# 03-4G.net
KiCad netlist of a schematic drawn in Altium Designer
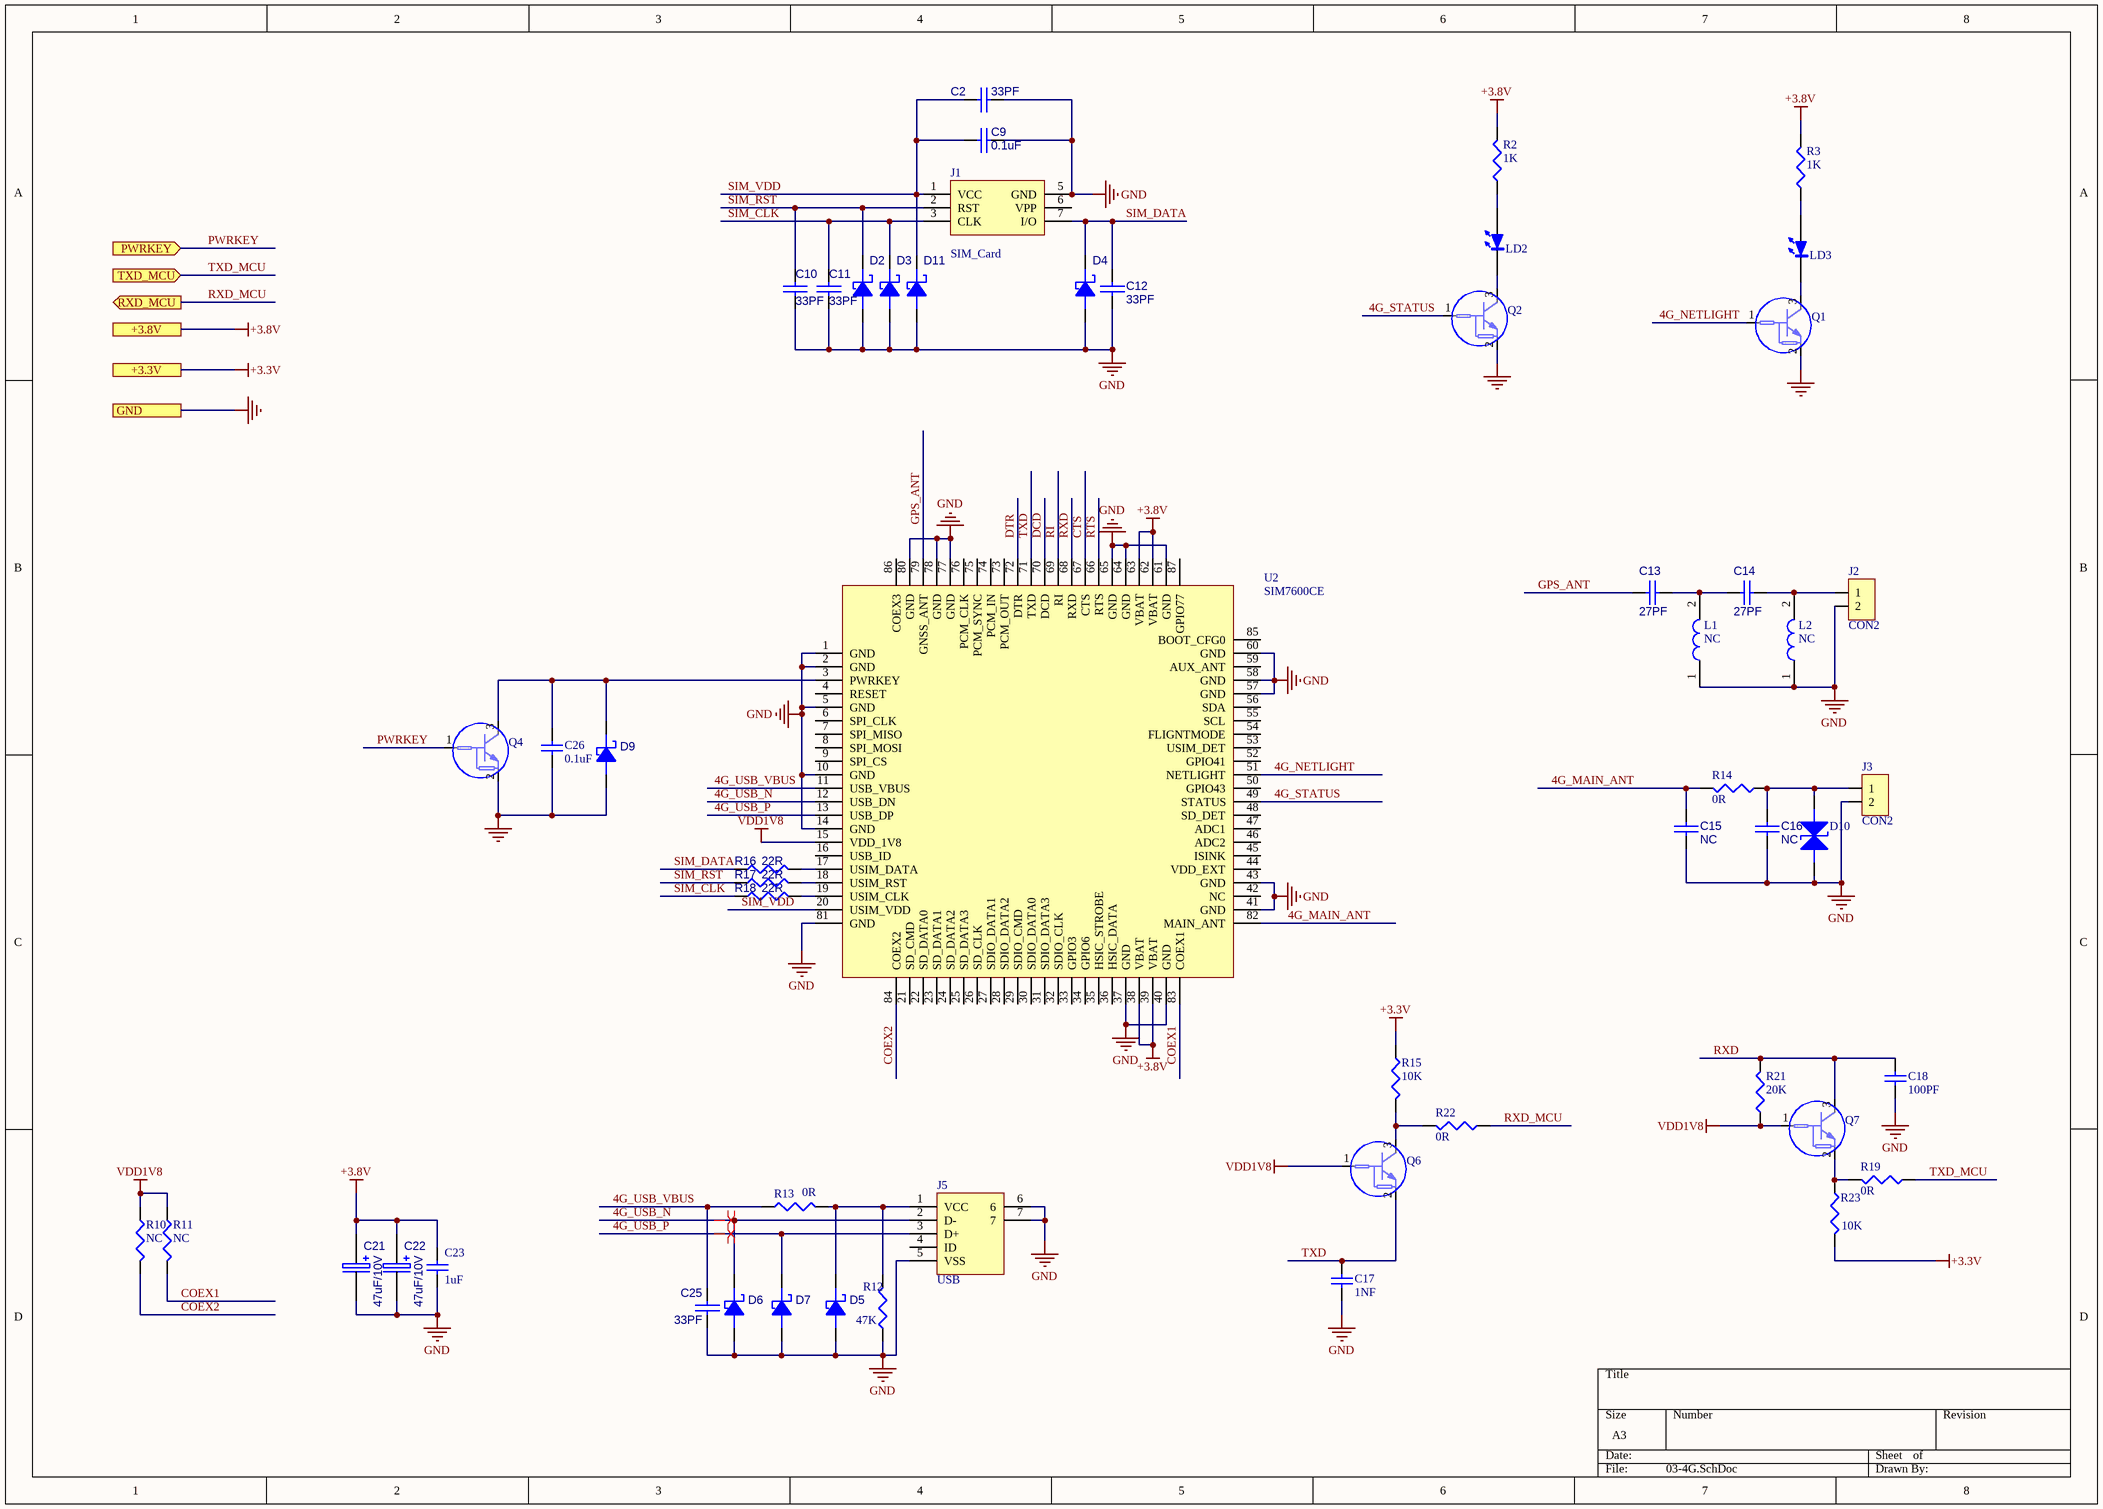
[diagram p0: 03-4G.SchDoc]

(export (version "E")
  (design (tool "Eeschema 10.0.6"))
  (components
    (comp (ref "C2")
      (value "33PF")
      (footprint "0603_C")
      (description "CAP")
      (libsource (lib "") (part "CAP_1"))
    )
    (comp (ref "C9")
      (value "0.1uF")
      (footprint "0603_C")
      (description "CAP")
      (libsource (lib "") (part "CAP_1"))
    )
    (comp (ref "C10")
      (value "33PF")
      (footprint "0603_C")
      (description "CAP")
      (libsource (lib "*") (part "CAP"))
    )
    (comp (ref "C11")
      (value "33PF")
      (footprint "0603_C")
      (description "CAP")
      (libsource (lib "*") (part "CAP"))
    )
    (comp (ref "C12")
      (value "33PF")
      (footprint "0603_C")
      (description "CAP")
      (libsource (lib "*") (part "CAP"))
    )
    (comp (ref "C13")
      (value "27PF")
      (footprint "0402")
      (description "CAP")
      (libsource (lib "") (part "CAP_1"))
    )
    (comp (ref "C14")
      (value "27PF")
      (footprint "0402")
      (description "CAP")
      (libsource (lib "") (part "CAP_1"))
    )
    (comp (ref "C15") (value "NC") (footprint "0402") (description "CAP") (libsource (lib "*") (part "CAP")))
    (comp (ref "C16") (value "NC") (footprint "0402") (description "CAP") (libsource (lib "*") (part "CAP")))
    (comp (ref "C17")
      (value "1NF")
      (footprint "0603_C")
      (description "Capacitor")
      (fields (field (name "PUBLISHER") "Altium Limited"))
      (libsource (lib "EP_MCB_V3.00") (part "Cap Semi"))
    )
    (comp (ref "C18")
      (value "100PF")
      (footprint "0603_C")
      (description "Capacitor")
      (fields (field (name "PUBLISHER") "Altium Limited"))
      (libsource (lib "EP_MCB_V3.00") (part "Cap Semi"))
    )
    (comp (ref "C21")
      (value "47uF/10V")
      (footprint "C_TAN_B")
      (description "E-CAP")
      (libsource (lib "*") (part "ECAP"))
    )
    (comp (ref "C22")
      (value "47uF/10V")
      (footprint "C_TAN_B")
      (description "E-CAP")
      (libsource (lib "*") (part "ECAP"))
    )
    (comp (ref "C23")
      (value "1uF")
      (footprint "0603_C")
      (description "Capacitor")
      (fields (field (name "PUBLISHER") "Altium Limited"))
      (libsource (lib "EP_MCB_V3.00") (part "Cap Semi"))
    )
    (comp (ref "C25")
      (value "33PF")
      (footprint "0603_C")
      (description "CAP")
      (libsource (lib "*") (part "CAP"))
    )
    (comp (ref "C26")
      (value "0.1uF")
      (footprint "0603_C")
      (description "Capacitor")
      (fields (field (name "PUBLISHER") "Altium Limited"))
      (libsource (lib "EP_MCB_V3.00") (part "Cap Semi"))
    )
    (comp (ref "D2")
      (value "ESD9M5.0ST5G")
      (footprint "SOD-923")
      (libsource (lib "EP_MCB_V4.1") (part "DIODE SCHOTTKY"))
    )
    (comp (ref "D3")
      (value "ESD9M5.0ST5G")
      (footprint "SOD-923")
      (libsource (lib "EP_MCB_V4.1") (part "DIODE SCHOTTKY"))
    )
    (comp (ref "D4")
      (value "ESD9M5.0ST5G")
      (footprint "SOD-923")
      (libsource (lib "EP_MCB_V4.1") (part "DIODE SCHOTTKY"))
    )
    (comp (ref "D5")
      (value "PESD12VS1UB")
      (footprint "SOD523")
      (libsource (lib "EP_MCB_V4.1") (part "DIODE SCHOTTKY"))
    )
    (comp (ref "D6")
      (value "ESD9L5.0ST5G")
      (footprint "SOD-923")
      (libsource (lib "EP_MCB_V4.1") (part "DIODE SCHOTTKY"))
    )
    (comp (ref "D7")
      (value "ESD9L5.0ST5G")
      (footprint "SOD-923")
      (libsource (lib "EP_MCB_V4.1") (part "DIODE SCHOTTKY"))
    )
    (comp (ref "D9")
      (value "ESD9M5.0ST5G")
      (footprint "SOD-923")
      (libsource (lib "EP_MCB_V4.1") (part "DIODE SCHOTTKY"))
    )
    (comp (ref "D10")
      (value "LXES15AAA1-153")
      (footprint "0402")
      (libsource (lib "MySchlib") (part "DIODE TVS BI-DIR"))
    )
    (comp (ref "D11")
      (value "ESD9M5.0ST5G")
      (footprint "SOD-923")
      (libsource (lib "EP_MCB_V4.1") (part "DIODE SCHOTTKY"))
    )
    (comp (ref "J1")
      (value "SIM_Card")
      (footprint "MicroSIM-6")
      (libsource (lib "MySchlib") (part "SIM_Card"))
    )
    (comp (ref "J2") (value "CON2") (footprint "RF-Z") (libsource (lib "MySchlib") (part "CON2")))
    (comp (ref "J3") (value "CON2") (footprint "RF-Z") (libsource (lib "MySchlib") (part "CON2")))
    (comp (ref "J5") (value "USB") (libsource (lib "MySchlib") (part "USB-M")))
    (comp (ref "L1") (value "NC") (footprint "0402") (libsource (lib "MySchlib") (part "L")))
    (comp (ref "L2") (value "NC") (footprint "0402") (libsource (lib "MySchlib") (part "L")))
    (comp (ref "LD2")
      (value "WHITE")
      (footprint "LED_0603")
      (description "LED")
      (libsource (lib "*") (part "LED"))
    )
    (comp (ref "LD3")
      (value "WHITE")
      (footprint "LED_0603")
      (description "LED")
      (libsource (lib "*") (part "LED"))
    )
    (comp (ref "Q1")
      (value "DTC143ZEBTL")
      (footprint "SC-85")
      (libsource (lib "MySchlib") (part "DTC143ZETL"))
    )
    (comp (ref "Q2")
      (value "DTC143ZEBTL")
      (footprint "SC-85")
      (libsource (lib "MySchlib") (part "DTC143ZETL"))
    )
    (comp (ref "Q4")
      (value "DTC143ZEBTL")
      (footprint "SC-85")
      (libsource (lib "MySchlib") (part "DTC143ZETL"))
    )
    (comp (ref "Q6")
      (value "DTC143ZEBTL")
      (footprint "SC-85")
      (libsource (lib "MySchlib") (part "DTC143ZETL"))
    )
    (comp (ref "Q7")
      (value "DTC143ZEBTL")
      (footprint "SC-85")
      (libsource (lib "MySchlib") (part "DTC143ZETL"))
    )
    (comp (ref "R2") (value "1K") (footprint "0603_R") (libsource (lib "MySchlib") (part "RES1")))
    (comp (ref "R3") (value "1K") (footprint "0603_R") (libsource (lib "MySchlib") (part "RES1")))
    (comp (ref "R10") (value "NC") (footprint "0603_R") (libsource (lib "MySchlib") (part "RES1")))
    (comp (ref "R11") (value "NC") (footprint "0603_R") (libsource (lib "MySchlib") (part "RES1")))
    (comp (ref "R12") (value "47K") (footprint "0603_R") (libsource (lib "MySchlib") (part "RES1")))
    (comp (ref "R13") (value "0R") (footprint "0402") (libsource (lib "MySchlib") (part "RES1")))
    (comp (ref "R14") (value "0R") (footprint "0402") (libsource (lib "MySchlib") (part "RES1")))
    (comp (ref "R15") (value "10K") (footprint "0603_R") (libsource (lib "MySchlib") (part "RES1")))
    (comp (ref "R16")
      (value "22R")
      (footprint "0603_R")
      (description "RESISTOR")
      (libsource (lib "*") (part "R0.25W"))
    )
    (comp (ref "R17")
      (value "22R")
      (footprint "0603_R")
      (description "RESISTOR")
      (libsource (lib "*") (part "R0.25W"))
    )
    (comp (ref "R18")
      (value "22R")
      (footprint "0603_R")
      (description "RESISTOR")
      (libsource (lib "*") (part "R0.25W"))
    )
    (comp (ref "R19") (value "0R") (footprint "0603_R") (libsource (lib "MySchlib") (part "RES1")))
    (comp (ref "R21") (value "20K") (footprint "0603_R") (libsource (lib "MySchlib") (part "RES1")))
    (comp (ref "R22") (value "0R") (footprint "0603_R") (libsource (lib "MySchlib") (part "RES1")))
    (comp (ref "R23") (value "10K") (footprint "0603_R") (libsource (lib "MySchlib") (part "RES1")))
    (comp (ref "U2") (value "SIM7600CE") (footprint "SIM7600") (libsource (lib "MySchlib") (part "SIM7600")))
  )
  (nets
    (net (code "1") (name "+3.3V") (class "Default")
      (node (ref "R15") (pin "1") (pinfunction "1_1") (pintype "passive"))
      (node (ref "R23") (pin "2") (pinfunction "2_2") (pintype "passive"))
    )
    (net (code "2") (name "+3.8V") (class "Default")
      (node (ref "C21") (pin "1") (pinfunction "+_1") (pintype "passive"))
      (node (ref "C22") (pin "1") (pinfunction "+_1") (pintype "passive"))
      (node (ref "C23") (pin "2") (pinfunction "2_2") (pintype "passive"))
      (node (ref "R2") (pin "1") (pinfunction "1_1") (pintype "passive"))
      (node (ref "R3") (pin "1") (pinfunction "1_1") (pintype "passive"))
      (node (ref "U2") (pin "38") (pinfunction "VBAT_38") (pintype "passive"))
      (node (ref "U2") (pin "39") (pinfunction "VBAT_39") (pintype "passive"))
      (node (ref "U2") (pin "62") (pinfunction "VBAT_62") (pintype "passive"))
      (node (ref "U2") (pin "63") (pinfunction "VBAT_63") (pintype "passive"))
    )
    (net (code "3") (name "/4G_MAIN_ANT") (class "Default")
      (node (ref "C15") (pin "2") (pinfunction "2_2") (pintype "passive"))
      (node (ref "R14") (pin "2") (pinfunction "2_2") (pintype "passive"))
      (node (ref "U2") (pin "82") (pinfunction "MAIN_ANT_82") (pintype "passive"))
    )
    (net (code "4") (name "/4G_NETLIGHT") (class "Default")
      (node (ref "Q1") (pin "1") (pinfunction "B_1") (pintype "passive"))
      (node (ref "U2") (pin "51") (pinfunction "NETLIGHT_51") (pintype "passive"))
    )
    (net (code "5") (name "/4G_STATUS") (class "Default")
      (node (ref "Q2") (pin "1") (pinfunction "B_1") (pintype "passive"))
      (node (ref "U2") (pin "49") (pinfunction "STATUS_49") (pintype "passive"))
    )
    (net (code "6") (name "/4G_USB_N") (class "Default")
      (node (ref "D6") (pin "2") (pinfunction "CATHODE_2") (pintype "passive"))
      (node (ref "J5") (pin "2") (pinfunction "D-_2") (pintype "passive"))
      (node (ref "U2") (pin "12") (pinfunction "USB_DN_12") (pintype "passive"))
    )
    (net (code "7") (name "/4G_USB_P") (class "Default")
      (node (ref "D7") (pin "2") (pinfunction "CATHODE_2") (pintype "passive"))
      (node (ref "J5") (pin "3") (pinfunction "D+_3") (pintype "passive"))
      (node (ref "U2") (pin "13") (pinfunction "USB_DP_13") (pintype "passive"))
    )
    (net (code "8") (name "/4G_USB_VBUS") (class "Default")
      (node (ref "C25") (pin "1") (pinfunction "1_1") (pintype "passive"))
      (node (ref "R13") (pin "1") (pinfunction "1_1") (pintype "passive"))
      (node (ref "U2") (pin "11") (pinfunction "USB_VBUS_11") (pintype "passive"))
    )
    (net (code "9") (name "/COEX1") (class "Default")
      (node (ref "R11") (pin "2") (pinfunction "2_2") (pintype "passive"))
      (node (ref "U2") (pin "83") (pinfunction "COEX1_83") (pintype "passive"))
    )
    (net (code "10") (name "/COEX2") (class "Default")
      (node (ref "R10") (pin "2") (pinfunction "2_2") (pintype "passive"))
      (node (ref "U2") (pin "84") (pinfunction "COEX2_84") (pintype "passive"))
    )
    (net (code "11") (name "/CTS") (class "Default")
      (node (ref "U2") (pin "67") (pinfunction "CTS_67") (pintype "passive"))
    )
    (net (code "12") (name "/DCD") (class "Default")
      (node (ref "U2") (pin "70") (pinfunction "DCD_70") (pintype "passive"))
    )
    (net (code "13") (name "/DTR") (class "Default")
      (node (ref "U2") (pin "72") (pinfunction "DTR_72") (pintype "passive"))
    )
    (net (code "14") (name "/GPS_ANT") (class "Default")
      (node (ref "C13") (pin "1") (pinfunction "1_1") (pintype "passive"))
      (node (ref "U2") (pin "79") (pinfunction "GNSS_ANT_79") (pintype "passive"))
    )
    (net (code "15") (name "/PWRKEY") (class "Default")
      (node (ref "Q4") (pin "1") (pinfunction "B_1") (pintype "passive"))
    )
    (net (code "16") (name "/RI") (class "Default")
      (node (ref "U2") (pin "69") (pinfunction "RI_69") (pintype "passive"))
    )
    (net (code "17") (name "/RTS") (class "Default")
      (node (ref "U2") (pin "66") (pinfunction "RTS_66") (pintype "passive"))
    )
    (net (code "18") (name "/RXD") (class "Default")
      (node (ref "C18") (pin "2") (pinfunction "2_2") (pintype "passive"))
      (node (ref "Q7") (pin "3") (pinfunction "C_3") (pintype "passive"))
      (node (ref "R21") (pin "2") (pinfunction "2_2") (pintype "passive"))
      (node (ref "U2") (pin "68") (pinfunction "RXD_68") (pintype "passive"))
    )
    (net (code "19") (name "/RXD_MCU") (class "Default")
      (node (ref "R22") (pin "1") (pinfunction "1_1") (pintype "passive"))
    )
    (net (code "20") (name "/SIM_CLK") (class "Default")
      (node (ref "C11") (pin "2") (pinfunction "2_2") (pintype "passive"))
      (node (ref "D3") (pin "2") (pinfunction "CATHODE_2") (pintype "passive"))
      (node (ref "J1") (pin "3") (pinfunction "CLK_3") (pintype "passive"))
      (node (ref "R18") (pin "1") (pinfunction "1_1") (pintype "passive"))
    )
    (net (code "21") (name "/SIM_DATA") (class "Default")
      (node (ref "C12") (pin "2") (pinfunction "2_2") (pintype "passive"))
      (node (ref "D4") (pin "2") (pinfunction "CATHODE_2") (pintype "passive"))
      (node (ref "J1") (pin "7") (pinfunction "I/O_7") (pintype "passive"))
      (node (ref "R16") (pin "1") (pinfunction "1_1") (pintype "passive"))
    )
    (net (code "22") (name "/SIM_RST") (class "Default")
      (node (ref "C10") (pin "2") (pinfunction "2_2") (pintype "passive"))
      (node (ref "D2") (pin "2") (pinfunction "CATHODE_2") (pintype "passive"))
      (node (ref "J1") (pin "2") (pinfunction "RST_2") (pintype "passive"))
      (node (ref "R17") (pin "1") (pinfunction "1_1") (pintype "passive"))
    )
    (net (code "23") (name "/SIM_VDD") (class "Default")
      (node (ref "C2") (pin "1") (pinfunction "1_1") (pintype "passive"))
      (node (ref "C9") (pin "1") (pinfunction "1_1") (pintype "passive"))
      (node (ref "D11") (pin "2") (pinfunction "CATHODE_2") (pintype "passive"))
      (node (ref "J1") (pin "1") (pinfunction "VCC_1") (pintype "passive"))
      (node (ref "U2") (pin "20") (pinfunction "USIM_VDD_20") (pintype "passive"))
    )
    (net (code "24") (name "/TXD") (class "Default")
      (node (ref "C17") (pin "1") (pinfunction "1_1") (pintype "passive"))
      (node (ref "Q6") (pin "2") (pinfunction "E_2") (pintype "passive"))
      (node (ref "U2") (pin "71") (pinfunction "TXD_71") (pintype "passive"))
    )
    (net (code "25") (name "/TXD_MCU") (class "Default")
      (node (ref "R19") (pin "1") (pinfunction "1_1") (pintype "passive"))
    )
    (net (code "26") (name "GND") (class "Default")
      (node (ref "C10") (pin "1") (pinfunction "1_1") (pintype "passive"))
      (node (ref "C11") (pin "1") (pinfunction "1_1") (pintype "passive"))
      (node (ref "C12") (pin "1") (pinfunction "1_1") (pintype "passive"))
      (node (ref "C15") (pin "1") (pinfunction "1_1") (pintype "passive"))
      (node (ref "C16") (pin "1") (pinfunction "1_1") (pintype "passive"))
      (node (ref "C17") (pin "2") (pinfunction "2_2") (pintype "passive"))
      (node (ref "C18") (pin "1") (pinfunction "1_1") (pintype "passive"))
      (node (ref "C2") (pin "2") (pinfunction "2_2") (pintype "passive"))
      (node (ref "C21") (pin "2") (pinfunction "-_2") (pintype "passive"))
      (node (ref "C22") (pin "2") (pinfunction "-_2") (pintype "passive"))
      (node (ref "C23") (pin "1") (pinfunction "1_1") (pintype "passive"))
      (node (ref "C25") (pin "2") (pinfunction "2_2") (pintype "passive"))
      (node (ref "C26") (pin "1") (pinfunction "1_1") (pintype "passive"))
      (node (ref "C9") (pin "2") (pinfunction "2_2") (pintype "passive"))
      (node (ref "D10") (pin "2") (pinfunction "2_2") (pintype "passive"))
      (node (ref "D11") (pin "1") (pinfunction "ANODE_1") (pintype "passive"))
      (node (ref "D2") (pin "1") (pinfunction "ANODE_1") (pintype "passive"))
      (node (ref "D3") (pin "1") (pinfunction "ANODE_1") (pintype "passive"))
      (node (ref "D4") (pin "1") (pinfunction "ANODE_1") (pintype "passive"))
      (node (ref "D5") (pin "1") (pinfunction "ANODE_1") (pintype "passive"))
      (node (ref "D6") (pin "1") (pinfunction "ANODE_1") (pintype "passive"))
      (node (ref "D7") (pin "1") (pinfunction "ANODE_1") (pintype "passive"))
      (node (ref "D9") (pin "1") (pinfunction "ANODE_1") (pintype "passive"))
      (node (ref "J1") (pin "5") (pinfunction "GND_5") (pintype "passive"))
      (node (ref "J2") (pin "2") (pinfunction "2_2") (pintype "passive"))
      (node (ref "J3") (pin "2") (pinfunction "2_2") (pintype "passive"))
      (node (ref "J5") (pin "5") (pinfunction "VSS_5") (pintype "passive"))
      (node (ref "J5") (pin "6") (pinfunction "6_6") (pintype "passive"))
      (node (ref "J5") (pin "7") (pinfunction "7_7") (pintype "passive"))
      (node (ref "L1") (pin "1") (pinfunction "1_1") (pintype "passive"))
      (node (ref "L2") (pin "1") (pinfunction "1_1") (pintype "passive"))
      (node (ref "Q1") (pin "2") (pinfunction "E_2") (pintype "passive"))
      (node (ref "Q2") (pin "2") (pinfunction "E_2") (pintype "passive"))
      (node (ref "Q4") (pin "2") (pinfunction "E_2") (pintype "passive"))
      (node (ref "R12") (pin "2") (pinfunction "2_2") (pintype "passive"))
      (node (ref "U2") (pin "1") (pinfunction "GND_1") (pintype "passive"))
      (node (ref "U2") (pin "10") (pinfunction "GND_10") (pintype "passive"))
      (node (ref "U2") (pin "14") (pinfunction "GND_14") (pintype "passive"))
      (node (ref "U2") (pin "2") (pinfunction "GND_2") (pintype "passive"))
      (node (ref "U2") (pin "37") (pinfunction "GND_37") (pintype "passive"))
      (node (ref "U2") (pin "40") (pinfunction "GND_40") (pintype "passive"))
      (node (ref "U2") (pin "41") (pinfunction "GND_41") (pintype "passive"))
      (node (ref "U2") (pin "43") (pinfunction "GND_43") (pintype "passive"))
      (node (ref "U2") (pin "5") (pinfunction "GND_5") (pintype "passive"))
      (node (ref "U2") (pin "57") (pinfunction "GND_57") (pintype "passive"))
      (node (ref "U2") (pin "58") (pinfunction "GND_58") (pintype "passive"))
      (node (ref "U2") (pin "60") (pinfunction "GND_60") (pintype "passive"))
      (node (ref "U2") (pin "61") (pinfunction "GND_61") (pintype "passive"))
      (node (ref "U2") (pin "64") (pinfunction "GND_64") (pintype "passive"))
      (node (ref "U2") (pin "65") (pinfunction "GND_65") (pintype "passive"))
      (node (ref "U2") (pin "77") (pinfunction "GND_77") (pintype "passive"))
      (node (ref "U2") (pin "78") (pinfunction "GND_78") (pintype "passive"))
      (node (ref "U2") (pin "80") (pinfunction "GND_80") (pintype "passive"))
      (node (ref "U2") (pin "81") (pinfunction "GND_81") (pintype "passive"))
    )
    (net (code "27") (name "Net-(C13-Pad2)") (class "Default")
      (node (ref "C13") (pin "2") (pinfunction "2_2") (pintype "passive"))
      (node (ref "C14") (pin "1") (pinfunction "1_1") (pintype "passive"))
      (node (ref "L1") (pin "2") (pinfunction "2_2") (pintype "passive"))
    )
    (net (code "28") (name "Net-(C14-Pad2)") (class "Default")
      (node (ref "C14") (pin "2") (pinfunction "2_2") (pintype "passive"))
      (node (ref "J2") (pin "1") (pinfunction "1_1") (pintype "passive"))
      (node (ref "L2") (pin "2") (pinfunction "2_2") (pintype "passive"))
    )
    (net (code "29") (name "Net-(C16-Pad2)") (class "Default")
      (node (ref "C16") (pin "2") (pinfunction "2_2") (pintype "passive"))
      (node (ref "D10") (pin "1") (pinfunction "1_1") (pintype "passive"))
      (node (ref "J3") (pin "1") (pinfunction "1_1") (pintype "passive"))
      (node (ref "R14") (pin "1") (pinfunction "1_1") (pintype "passive"))
    )
    (net (code "30") (name "Net-(D5-CATHODE)") (class "Default")
      (node (ref "D5") (pin "2") (pinfunction "CATHODE_2") (pintype "passive"))
      (node (ref "J5") (pin "1") (pinfunction "VCC_1") (pintype "passive"))
      (node (ref "R12") (pin "1") (pinfunction "1_1") (pintype "passive"))
      (node (ref "R13") (pin "2") (pinfunction "2_2") (pintype "passive"))
    )
    (net (code "31") (name "Net-(D9-CATHODE)") (class "Default")
      (node (ref "C26") (pin "2") (pinfunction "2_2") (pintype "passive"))
      (node (ref "D9") (pin "2") (pinfunction "CATHODE_2") (pintype "passive"))
      (node (ref "Q4") (pin "3") (pinfunction "C_3") (pintype "passive"))
      (node (ref "U2") (pin "3") (pinfunction "PWRKEY_3") (pintype "passive"))
    )
    (net (code "32") (name "Net-(LD2-PadA)") (class "Default")
      (node (ref "LD2") (pin "A") (pinfunction "A_A") (pintype "passive"))
      (node (ref "R2") (pin "2") (pinfunction "2_2") (pintype "passive"))
    )
    (net (code "33") (name "Net-(LD3-PadA)") (class "Default")
      (node (ref "LD3") (pin "A") (pinfunction "A_A") (pintype "passive"))
      (node (ref "R3") (pin "2") (pinfunction "2_2") (pintype "passive"))
    )
    (net (code "34") (name "Net-(Q1-C)") (class "Default")
      (node (ref "LD3") (pin "K") (pinfunction "K_K") (pintype "passive"))
      (node (ref "Q1") (pin "3") (pinfunction "C_3") (pintype "passive"))
    )
    (net (code "35") (name "Net-(Q2-C)") (class "Default")
      (node (ref "LD2") (pin "K") (pinfunction "K_K") (pintype "passive"))
      (node (ref "Q2") (pin "3") (pinfunction "C_3") (pintype "passive"))
    )
    (net (code "36") (name "Net-(Q6-C)") (class "Default")
      (node (ref "Q6") (pin "3") (pinfunction "C_3") (pintype "passive"))
      (node (ref "R15") (pin "2") (pinfunction "2_2") (pintype "passive"))
      (node (ref "R22") (pin "2") (pinfunction "2_2") (pintype "passive"))
    )
    (net (code "37") (name "Net-(Q7-E)") (class "Default")
      (node (ref "Q7") (pin "2") (pinfunction "E_2") (pintype "passive"))
      (node (ref "R19") (pin "2") (pinfunction "2_2") (pintype "passive"))
      (node (ref "R23") (pin "1") (pinfunction "1_1") (pintype "passive"))
    )
    (net (code "38") (name "Net-(U2-USIM_CLK)") (class "Default")
      (node (ref "R18") (pin "2") (pinfunction "2_2") (pintype "passive"))
      (node (ref "U2") (pin "19") (pinfunction "USIM_CLK_19") (pintype "passive"))
    )
    (net (code "39") (name "Net-(U2-USIM_DATA)") (class "Default")
      (node (ref "R16") (pin "2") (pinfunction "2_2") (pintype "passive"))
      (node (ref "U2") (pin "17") (pinfunction "USIM_DATA_17") (pintype "passive"))
    )
    (net (code "40") (name "Net-(U2-USIM_RST)") (class "Default")
      (node (ref "R17") (pin "2") (pinfunction "2_2") (pintype "passive"))
      (node (ref "U2") (pin "18") (pinfunction "USIM_RST_18") (pintype "passive"))
    )
    (net (code "41") (name "VDD1V8") (class "Default")
      (node (ref "Q6") (pin "1") (pinfunction "B_1") (pintype "passive"))
      (node (ref "Q7") (pin "1") (pinfunction "B_1") (pintype "passive"))
      (node (ref "R10") (pin "1") (pinfunction "1_1") (pintype "passive"))
      (node (ref "R11") (pin "1") (pinfunction "1_1") (pintype "passive"))
      (node (ref "R21") (pin "1") (pinfunction "1_1") (pintype "passive"))
      (node (ref "U2") (pin "15") (pinfunction "VDD_1V8_15") (pintype "passive"))
    )
    (net (code "42") (name "unconnected-(J1-VPP-Pad6)") (class "Default")
      (node (ref "J1") (pin "6") (pinfunction "VPP_6") (pintype "passive"))
    )
    (net (code "43") (name "unconnected-(J5-ID-Pad4)") (class "Default")
      (node (ref "J5") (pin "4") (pinfunction "ID_4") (pintype "passive"))
    )
    (net (code "44") (name "unconnected-(U2-ADC1-Pad47)") (class "Default")
      (node (ref "U2") (pin "47") (pinfunction "ADC1_47") (pintype "passive"))
    )
    (net (code "45") (name "unconnected-(U2-ADC2-Pad46)") (class "Default")
      (node (ref "U2") (pin "46") (pinfunction "ADC2_46") (pintype "passive"))
    )
    (net (code "46") (name "unconnected-(U2-AUX_ANT-Pad59)") (class "Default")
      (node (ref "U2") (pin "59") (pinfunction "AUX_ANT_59") (pintype "passive"))
    )
    (net (code "47") (name "unconnected-(U2-BOOT_CFG0-Pad85)") (class "Default")
      (node (ref "U2") (pin "85") (pinfunction "BOOT_CFG0_85") (pintype "passive"))
    )
    (net (code "48") (name "unconnected-(U2-COEX3-Pad86)") (class "Default")
      (node (ref "U2") (pin "86") (pinfunction "COEX3_86") (pintype "passive"))
    )
    (net (code "49") (name "unconnected-(U2-FLIGNTMODE-Pad54)") (class "Default")
      (node (ref "U2") (pin "54") (pinfunction "FLIGNTMODE_54") (pintype "passive"))
    )
    (net (code "50") (name "unconnected-(U2-GPIO3-Pad33)") (class "Default")
      (node (ref "U2") (pin "33") (pinfunction "GPIO3_33") (pintype "passive"))
    )
    (net (code "51") (name "unconnected-(U2-GPIO6-Pad34)") (class "Default")
      (node (ref "U2") (pin "34") (pinfunction "GPIO6_34") (pintype "passive"))
    )
    (net (code "52") (name "unconnected-(U2-GPIO41-Pad52)") (class "Default")
      (node (ref "U2") (pin "52") (pinfunction "GPIO41_52") (pintype "passive"))
    )
    (net (code "53") (name "unconnected-(U2-GPIO43-Pad50)") (class "Default")
      (node (ref "U2") (pin "50") (pinfunction "GPIO43_50") (pintype "passive"))
    )
    (net (code "54") (name "unconnected-(U2-GPIO77-Pad87)") (class "Default")
      (node (ref "U2") (pin "87") (pinfunction "GPIO77_87") (pintype "passive"))
    )
    (net (code "55") (name "unconnected-(U2-HSIC_DATA-Pad36)") (class "Default")
      (node (ref "U2") (pin "36") (pinfunction "HSIC_DATA_36") (pintype "passive"))
    )
    (net (code "56") (name "unconnected-(U2-HSIC_STROBE-Pad35)") (class "Default")
      (node (ref "U2") (pin "35") (pinfunction "HSIC_STROBE_35") (pintype "passive"))
    )
    (net (code "57") (name "unconnected-(U2-ISINK-Pad45)") (class "Default")
      (node (ref "U2") (pin "45") (pinfunction "ISINK_45") (pintype "passive"))
    )
    (net (code "58") (name "unconnected-(U2-NC-Pad42)") (class "Default")
      (node (ref "U2") (pin "42") (pinfunction "NC_42") (pintype "passive"))
    )
    (net (code "59") (name "unconnected-(U2-PCM_CLK-Pad76)") (class "Default")
      (node (ref "U2") (pin "76") (pinfunction "PCM_CLK_76") (pintype "passive"))
    )
    (net (code "60") (name "unconnected-(U2-PCM_IN-Pad74)") (class "Default")
      (node (ref "U2") (pin "74") (pinfunction "PCM_IN_74") (pintype "passive"))
    )
    (net (code "61") (name "unconnected-(U2-PCM_OUT-Pad73)") (class "Default")
      (node (ref "U2") (pin "73") (pinfunction "PCM_OUT_73") (pintype "passive"))
    )
    (net (code "62") (name "unconnected-(U2-PCM_SYNC-Pad75)") (class "Default")
      (node (ref "U2") (pin "75") (pinfunction "PCM_SYNC_75") (pintype "passive"))
    )
    (net (code "63") (name "unconnected-(U2-RESET-Pad4)") (class "Default")
      (node (ref "U2") (pin "4") (pinfunction "RESET_4") (pintype "passive"))
    )
    (net (code "64") (name "unconnected-(U2-SCL-Pad55)") (class "Default")
      (node (ref "U2") (pin "55") (pinfunction "SCL_55") (pintype "passive"))
    )
    (net (code "65") (name "unconnected-(U2-SDA-Pad56)") (class "Default")
      (node (ref "U2") (pin "56") (pinfunction "SDA_56") (pintype "passive"))
    )
    (net (code "66") (name "unconnected-(U2-SDIO_CLK-Pad32)") (class "Default")
      (node (ref "U2") (pin "32") (pinfunction "SDIO_CLK_32") (pintype "passive"))
    )
    (net (code "67") (name "unconnected-(U2-SDIO_CMD-Pad29)") (class "Default")
      (node (ref "U2") (pin "29") (pinfunction "SDIO_CMD_29") (pintype "passive"))
    )
    (net (code "68") (name "unconnected-(U2-SDIO_DATA0-Pad30)") (class "Default")
      (node (ref "U2") (pin "30") (pinfunction "SDIO_DATA0_30") (pintype "passive"))
    )
    (net (code "69") (name "unconnected-(U2-SDIO_DATA1-Pad27)") (class "Default")
      (node (ref "U2") (pin "27") (pinfunction "SDIO_DATA1_27") (pintype "passive"))
    )
    (net (code "70") (name "unconnected-(U2-SDIO_DATA2-Pad28)") (class "Default")
      (node (ref "U2") (pin "28") (pinfunction "SDIO_DATA2_28") (pintype "passive"))
    )
    (net (code "71") (name "unconnected-(U2-SDIO_DATA3-Pad31)") (class "Default")
      (node (ref "U2") (pin "31") (pinfunction "SDIO_DATA3_31") (pintype "passive"))
    )
    (net (code "72") (name "unconnected-(U2-SD_CLK-Pad26)") (class "Default")
      (node (ref "U2") (pin "26") (pinfunction "SD_CLK_26") (pintype "passive"))
    )
    (net (code "73") (name "unconnected-(U2-SD_CMD-Pad21)") (class "Default")
      (node (ref "U2") (pin "21") (pinfunction "SD_CMD_21") (pintype "passive"))
    )
    (net (code "74") (name "unconnected-(U2-SD_DATA0-Pad22)") (class "Default")
      (node (ref "U2") (pin "22") (pinfunction "SD_DATA0_22") (pintype "passive"))
    )
    (net (code "75") (name "unconnected-(U2-SD_DATA1-Pad23)") (class "Default")
      (node (ref "U2") (pin "23") (pinfunction "SD_DATA1_23") (pintype "passive"))
    )
    (net (code "76") (name "unconnected-(U2-SD_DATA2-Pad24)") (class "Default")
      (node (ref "U2") (pin "24") (pinfunction "SD_DATA2_24") (pintype "passive"))
    )
    (net (code "77") (name "unconnected-(U2-SD_DATA3-Pad25)") (class "Default")
      (node (ref "U2") (pin "25") (pinfunction "SD_DATA3_25") (pintype "passive"))
    )
    (net (code "78") (name "unconnected-(U2-SD_DET-Pad48)") (class "Default")
      (node (ref "U2") (pin "48") (pinfunction "SD_DET_48") (pintype "passive"))
    )
    (net (code "79") (name "unconnected-(U2-SPI_CLK-Pad6)") (class "Default")
      (node (ref "U2") (pin "6") (pinfunction "SPI_CLK_6") (pintype "passive"))
    )
    (net (code "80") (name "unconnected-(U2-SPI_CS-Pad9)") (class "Default")
      (node (ref "U2") (pin "9") (pinfunction "SPI_CS_9") (pintype "passive"))
    )
    (net (code "81") (name "unconnected-(U2-SPI_MISO-Pad7)") (class "Default")
      (node (ref "U2") (pin "7") (pinfunction "SPI_MISO_7") (pintype "passive"))
    )
    (net (code "82") (name "unconnected-(U2-SPI_MOSI-Pad8)") (class "Default")
      (node (ref "U2") (pin "8") (pinfunction "SPI_MOSI_8") (pintype "passive"))
    )
    (net (code "83") (name "unconnected-(U2-USB_ID-Pad16)") (class "Default")
      (node (ref "U2") (pin "16") (pinfunction "USB_ID_16") (pintype "passive"))
    )
    (net (code "84") (name "unconnected-(U2-USIM_DET-Pad53)") (class "Default")
      (node (ref "U2") (pin "53") (pinfunction "USIM_DET_53") (pintype "passive"))
    )
    (net (code "85") (name "unconnected-(U2-VDD_EXT-Pad44)") (class "Default")
      (node (ref "U2") (pin "44") (pinfunction "VDD_EXT_44") (pintype "passive"))
    )
  )
)
